# medal.net
KiCad netlist of a schematic drawn in EAGLE
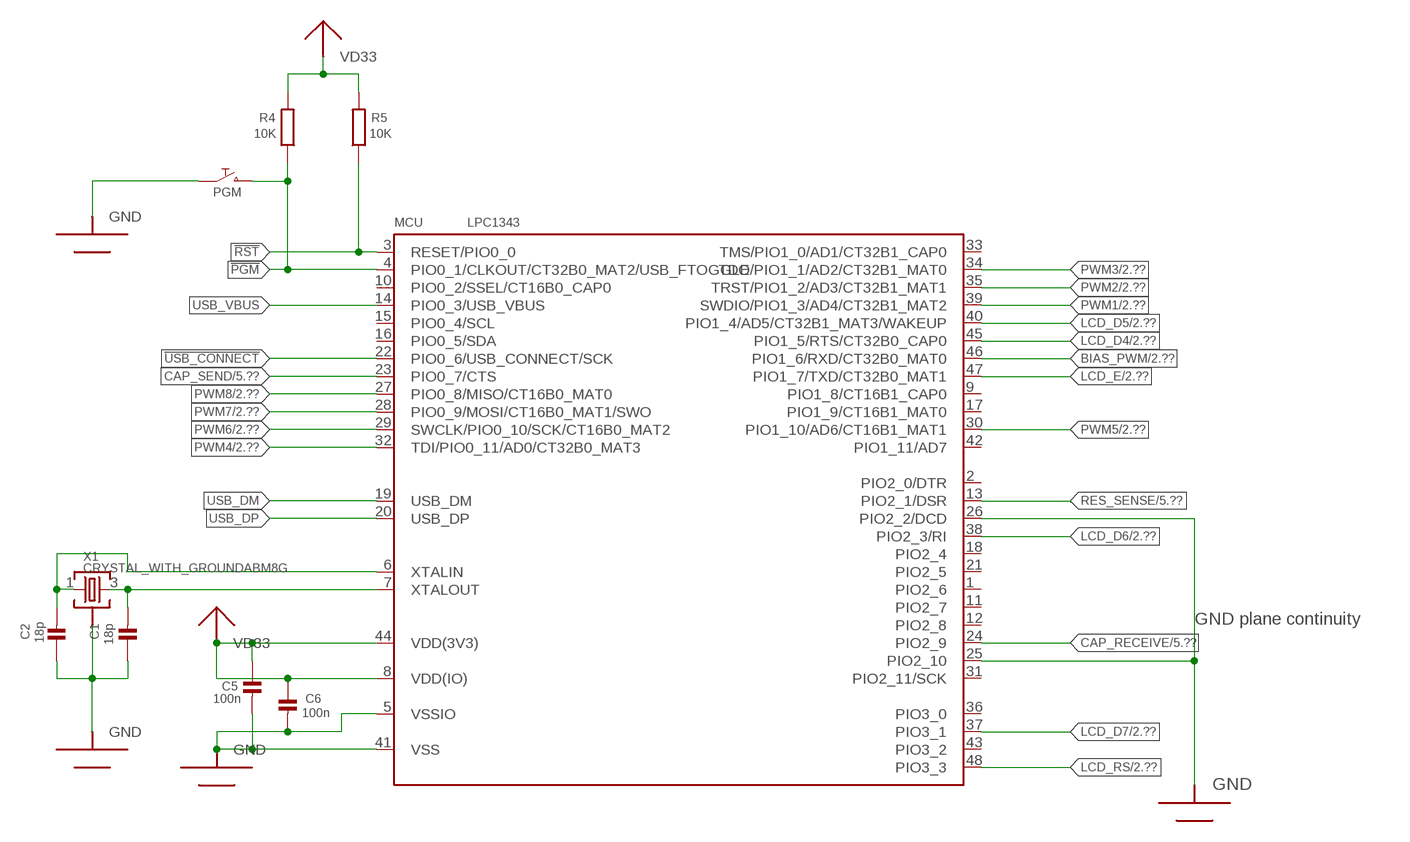
[diagram p0: schematic, sheet 1]
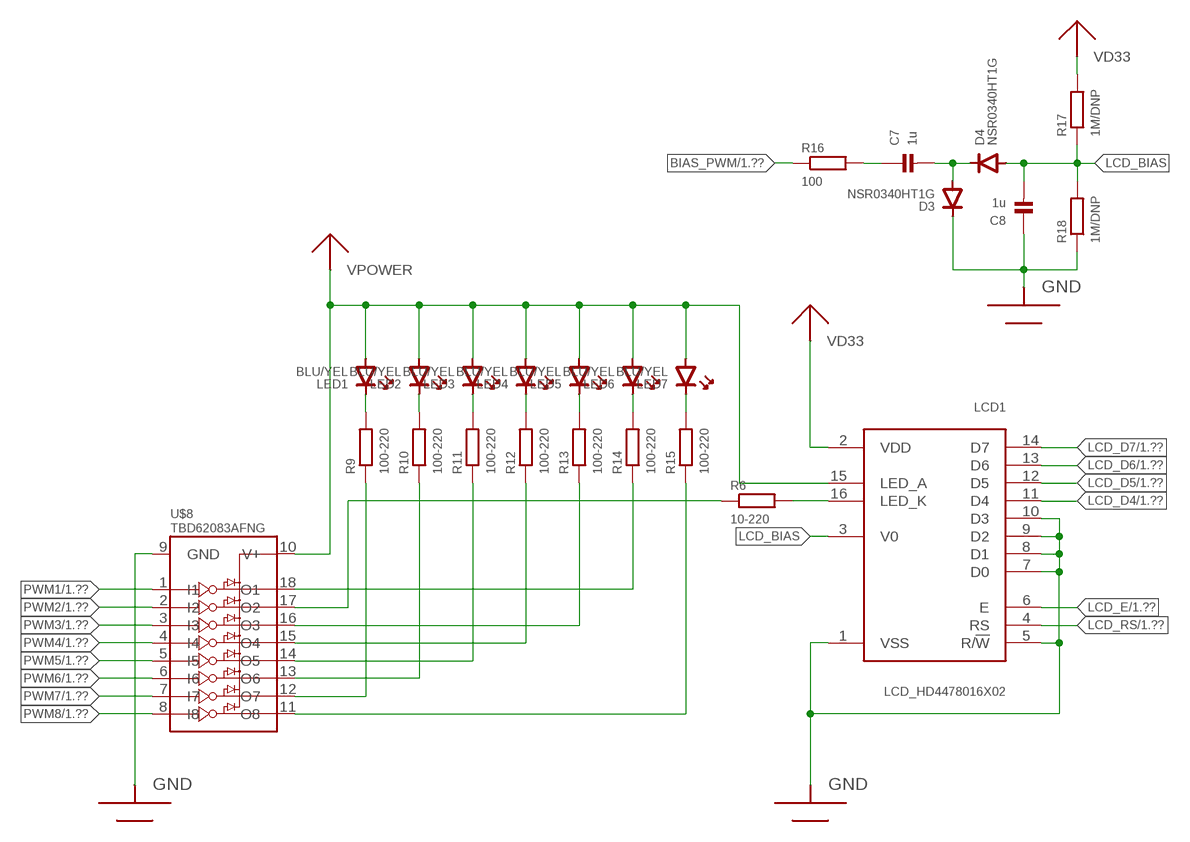
[diagram p1: schematic, sheet 2]
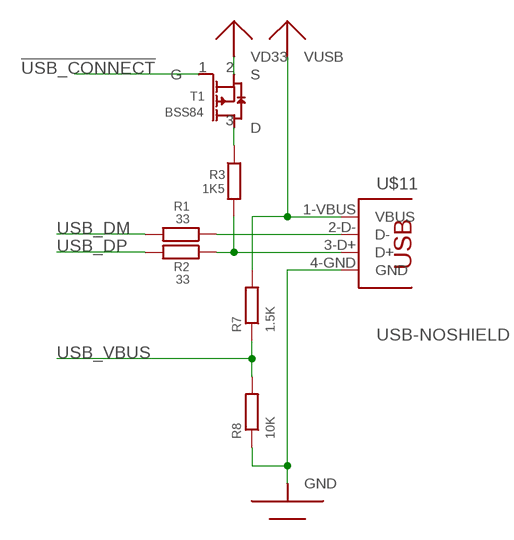
[diagram p2: schematic, sheet 3]
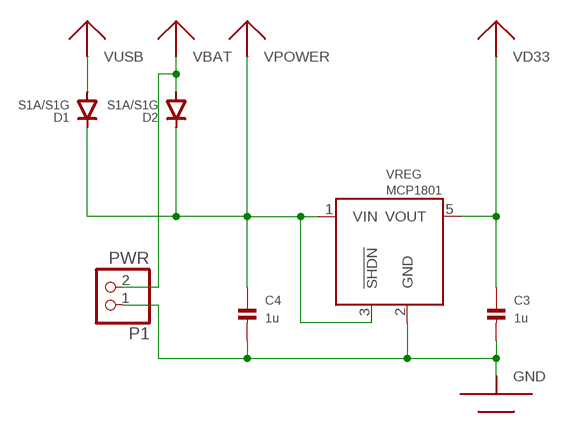
[diagram p3: schematic, sheet 4]
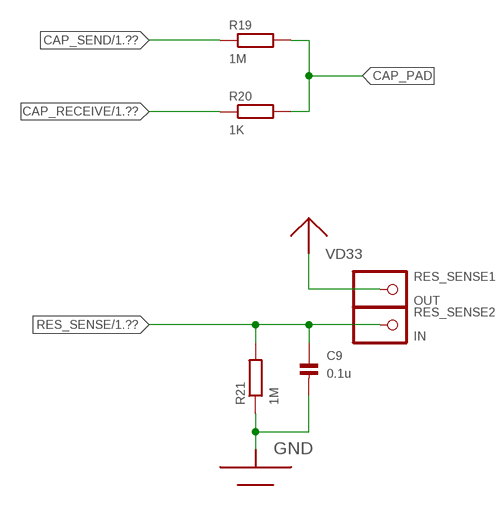
[diagram p4: schematic, sheet 5]

(export (version "E")
  (design (tool "Eeschema 10.0.6"))
  (components
    (comp (ref "C1")
      (value "18p")
      (footprint "eagle-import:0603-NOSILK")
      (libsource (lib "eagle-import") (part "CAP_CERAMIC0603-NOSILK"))
    )
    (comp (ref "C2")
      (value "18p")
      (footprint "eagle-import:0603-NOSILK")
      (libsource (lib "eagle-import") (part "CAP_CERAMIC0603-NOSILK"))
    )
    (comp (ref "C5")
      (value "100n")
      (footprint "eagle-import:0603-NOSILK")
      (libsource (lib "eagle-import") (part "CAP_CERAMIC0603-NOSILK"))
    )
    (comp (ref "C6")
      (value "100n")
      (footprint "eagle-import:0603-NOSILK")
      (libsource (lib "eagle-import") (part "CAP_CERAMIC0603-NOSILK"))
    )
    (comp (ref "MCU")
      (value "LPC1343")
      (footprint "eagle-import:QFP48-0.5-NOSILK")
      (libsource (lib "eagle-import") (part "LPC1343_QFPQFP_NOSILK"))
    )
    (comp (ref "PGM")
      (value "PUSHBUTTONKMR2XX-NOSILK")
      (footprint "eagle-import:CK-KMR2-NOSILK")
      (libsource (lib "eagle-import") (part "PUSHBUTTONKMR2XX-NOSILK"))
    )
    (comp (ref "R4")
      (value "10K")
      (footprint "eagle-import:0603-NOSILK")
      (libsource (lib "eagle-import") (part "R-EU_0603-NOSILK"))
    )
    (comp (ref "R5")
      (value "10K")
      (footprint "eagle-import:0603-NOSILK")
      (libsource (lib "eagle-import") (part "R-EU_0603-NOSILK"))
    )
    (comp (ref "X1")
      (value "CRYSTAL_WITH_GROUNDABM8G")
      (footprint "eagle-import:ABM8G")
      (libsource (lib "eagle-import") (part "CRYSTAL_WITH_GROUNDABM8G"))
    )
    (comp (ref "R1")
      (value "33")
      (footprint "eagle-import:0603-NOSILK")
      (libsource (lib "eagle-import") (part "R-EU_0603-NOSILK"))
    )
    (comp (ref "R2")
      (value "33")
      (footprint "eagle-import:0603-NOSILK")
      (libsource (lib "eagle-import") (part "R-EU_0603-NOSILK"))
    )
    (comp (ref "R3")
      (value "1K5")
      (footprint "eagle-import:0603-NOSILK")
      (libsource (lib "eagle-import") (part "R-EU_0603-NOSILK"))
    )
    (comp (ref "R7")
      (value "1.5K")
      (footprint "eagle-import:0603-NOSILK")
      (libsource (lib "eagle-import") (part "R-EU_0603-NOSILK"))
    )
    (comp (ref "R8")
      (value "10K")
      (footprint "eagle-import:0603-NOSILK")
      (libsource (lib "eagle-import") (part "R-EU_0603-NOSILK"))
    )
    (comp (ref "T1")
      (value "BSS84")
      (footprint "eagle-import:SOT23-NOPLACE")
      (libsource (lib "eagle-import") (part "PMOS_ENHSOT23-NOSILK"))
    )
    (comp (ref "U$11")
      (value "USB-NOSHIELD")
      (footprint "eagle-import:USB-A-PCB")
      (libsource (lib "eagle-import") (part "USB-NOSHIELD"))
    )
    (comp (ref "C7")
      (value "1u")
      (footprint "eagle-import:0603-NOSILK")
      (libsource (lib "eagle-import") (part "CAP_CERAMIC0603-NOSILK"))
    )
    (comp (ref "C8")
      (value "1u")
      (footprint "eagle-import:0603-NOSILK")
      (libsource (lib "eagle-import") (part "CAP_CERAMIC0603-NOSILK"))
    )
    (comp (ref "D3")
      (value "NSR0340HT1G")
      (footprint "eagle-import:SOD323R-NOPLACE")
      (libsource (lib "eagle-import") (part "DIODESOD323R-NOPLACE"))
    )
    (comp (ref "D4")
      (value "NSR0340HT1G")
      (footprint "eagle-import:SOD323R-NOPLACE")
      (libsource (lib "eagle-import") (part "DIODESOD323R-NOPLACE"))
    )
    (comp (ref "LCD1")
      (value "LCD_HD4478016X02")
      (footprint "eagle-import:LCD_16X02")
      (libsource (lib "eagle-import") (part "LCD_HD4478016X02"))
    )
    (comp (ref "LED1")
      (value "BLU/YEL")
      (footprint "eagle-import:0603_POLAR")
      (libsource (lib "eagle-import") (part "LED0603"))
    )
    (comp (ref "LED2")
      (value "BLU/YEL")
      (footprint "eagle-import:0603_POLAR")
      (libsource (lib "eagle-import") (part "LED0603"))
    )
    (comp (ref "LED3")
      (value "BLU/YEL")
      (footprint "eagle-import:0603_POLAR")
      (libsource (lib "eagle-import") (part "LED0603"))
    )
    (comp (ref "LED4")
      (value "BLU/YEL")
      (footprint "eagle-import:0603_POLAR")
      (libsource (lib "eagle-import") (part "LED0603"))
    )
    (comp (ref "LED5")
      (value "BLU/YEL")
      (footprint "eagle-import:0603_POLAR")
      (libsource (lib "eagle-import") (part "LED0603"))
    )
    (comp (ref "LED6")
      (value "BLU/YEL")
      (footprint "eagle-import:0603_POLAR")
      (libsource (lib "eagle-import") (part "LED0603"))
    )
    (comp (ref "LED7")
      (value "BLU/YEL")
      (footprint "eagle-import:0603_POLAR")
      (libsource (lib "eagle-import") (part "LED0603"))
    )
    (comp (ref "R6")
      (value "10-220")
      (footprint "eagle-import:1206-NOSILK")
      (libsource (lib "eagle-import") (part "R-EU_1206-NOSILK"))
    )
    (comp (ref "R9")
      (value "100-220")
      (footprint "eagle-import:0603-NOSILK")
      (libsource (lib "eagle-import") (part "R-EU_0603-NOSILK"))
    )
    (comp (ref "R10")
      (value "100-220")
      (footprint "eagle-import:0603-NOSILK")
      (libsource (lib "eagle-import") (part "R-EU_0603-NOSILK"))
    )
    (comp (ref "R11")
      (value "100-220")
      (footprint "eagle-import:0603-NOSILK")
      (libsource (lib "eagle-import") (part "R-EU_0603-NOSILK"))
    )
    (comp (ref "R12")
      (value "100-220")
      (footprint "eagle-import:0603-NOSILK")
      (libsource (lib "eagle-import") (part "R-EU_0603-NOSILK"))
    )
    (comp (ref "R13")
      (value "100-220")
      (footprint "eagle-import:0603-NOSILK")
      (libsource (lib "eagle-import") (part "R-EU_0603-NOSILK"))
    )
    (comp (ref "R14")
      (value "100-220")
      (footprint "eagle-import:0603-NOSILK")
      (libsource (lib "eagle-import") (part "R-EU_0603-NOSILK"))
    )
    (comp (ref "R15")
      (value "100-220")
      (footprint "eagle-import:0603-NOSILK")
      (libsource (lib "eagle-import") (part "R-EU_0603-NOSILK"))
    )
    (comp (ref "R16")
      (value "100")
      (footprint "eagle-import:0603-NOSILK")
      (libsource (lib "eagle-import") (part "R-EU_0603-NOSILK"))
    )
    (comp (ref "R17")
      (value "1M/DNP")
      (footprint "eagle-import:0603-NOSILK")
      (libsource (lib "eagle-import") (part "R-EU_0603-NOSILK"))
    )
    (comp (ref "R18")
      (value "1M/DNP")
      (footprint "eagle-import:0603-NOSILK")
      (libsource (lib "eagle-import") (part "R-EU_0603-NOSILK"))
    )
    (comp (ref "U$8")
      (value "TBD62083AFNG")
      (footprint "eagle-import:SSOP18-4.4-0.65-NOPLACE")
      (libsource (lib "eagle-import") (part "LOW_SIDE_DRIVERX8NOPLACE"))
    )
    (comp (ref "C9")
      (value "0.1u")
      (footprint "eagle-import:0603-NOSILK")
      (libsource (lib "eagle-import") (part "CAP_CERAMIC0603-NOSILK"))
    )
    (comp (ref "R19")
      (value "1M")
      (footprint "eagle-import:0603-NOSILK")
      (libsource (lib "eagle-import") (part "R-EU_0603-NOSILK"))
    )
    (comp (ref "R20")
      (value "1K")
      (footprint "eagle-import:0603-NOSILK")
      (libsource (lib "eagle-import") (part "R-EU_0603-NOSILK"))
    )
    (comp (ref "R21")
      (value "1M")
      (footprint "eagle-import:0603-NOSILK")
      (libsource (lib "eagle-import") (part "R-EU_0603-NOSILK"))
    )
    (comp (ref "RES_SENSE1")
      (value "OUT")
      (footprint "eagle-import:1X01_1MM_ROUND")
      (libsource (lib "eagle-import") (part "HEADER-1X1SMALL"))
    )
    (comp (ref "RES_SENSE2")
      (value "IN")
      (footprint "eagle-import:1X01_1MM_ROUND")
      (libsource (lib "eagle-import") (part "HEADER-1X1SMALL"))
    )
    (comp (ref "C3")
      (value "1u")
      (footprint "eagle-import:0603-NOSILK")
      (libsource (lib "eagle-import") (part "CAP_CERAMIC0603-NOSILK"))
    )
    (comp (ref "C4")
      (value "1u")
      (footprint "eagle-import:0603-NOSILK")
      (libsource (lib "eagle-import") (part "CAP_CERAMIC0603-NOSILK"))
    )
    (comp (ref "D1")
      (value "S1A/S1G")
      (footprint "eagle-import:DSMA-NOPLACE")
      (libsource (lib "eagle-import") (part "DIODEDSMA-NOPLACE"))
    )
    (comp (ref "D2")
      (value "S1A/S1G")
      (footprint "eagle-import:DSMA-NOPLACE")
      (libsource (lib "eagle-import") (part "DIODEDSMA-NOPLACE"))
    )
    (comp (ref "P1")
      (value "PWR")
      (footprint "eagle-import:1X02_ROUND")
      (libsource (lib "eagle-import") (part "HEADER-2ROUND"))
    )
    (comp (ref "VREG")
      (value "MCP1801")
      (footprint "eagle-import:SOT-23-5-NOSILK")
      (libsource (lib "eagle-import") (part "LDO_ENABLESOT-23-5-NOSILK"))
    )
  )
  (nets
    (net (code "1") (name "BIAS_PWM") (class "Default")
      (node (ref "MCU") (pin "46") (pinfunction "PIO1_6/RXD/CT32B0_MAT0_46") (pintype "bidirectional"))
      (node (ref "R16") (pin "1") (pinfunction "1_1") (pintype "passive"))
    )
    (net (code "2") (name "CAP_PAD") (class "Default")
      (node (ref "R19") (pin "2") (pinfunction "2_2") (pintype "passive"))
      (node (ref "R20") (pin "2") (pinfunction "2_2") (pintype "passive"))
    )
    (net (code "3") (name "CAP_RECEIVE") (class "Default")
      (node (ref "MCU") (pin "24") (pinfunction "PIO2_9_24") (pintype "bidirectional"))
      (node (ref "R20") (pin "1") (pinfunction "1_1") (pintype "passive"))
    )
    (net (code "4") (name "CAP_SEND") (class "Default")
      (node (ref "MCU") (pin "23") (pinfunction "PIO0_7/CTS_23") (pintype "bidirectional"))
      (node (ref "R19") (pin "1") (pinfunction "1_1") (pintype "passive"))
    )
    (net (code "5") (name "GND") (class "Default")
      (node (ref "C1") (pin "1") (pinfunction "P$1_1") (pintype "passive"))
      (node (ref "C2") (pin "1") (pinfunction "P$1_1") (pintype "passive"))
      (node (ref "C3") (pin "2") (pinfunction "P$2_2") (pintype "passive"))
      (node (ref "C4") (pin "2") (pinfunction "P$2_2") (pintype "passive"))
      (node (ref "C5") (pin "2") (pinfunction "P$2_2") (pintype "passive"))
      (node (ref "C6") (pin "2") (pinfunction "P$2_2") (pintype "passive"))
      (node (ref "C8") (pin "1") (pinfunction "P$1_1") (pintype "passive"))
      (node (ref "C9") (pin "2") (pinfunction "P$2_2") (pintype "passive"))
      (node (ref "D3") (pin "K") (pinfunction "CATHODE_K") (pintype "bidirectional"))
      (node (ref "LCD1") (pin "1") (pinfunction "VSS_1") (pintype "power_in"))
      (node (ref "LCD1") (pin "10") (pinfunction "D3_10") (pintype "bidirectional"))
      (node (ref "LCD1") (pin "5") (pinfunction "R/~{W}_5") (pintype "input"))
      (node (ref "LCD1") (pin "7") (pinfunction "D0_7") (pintype "bidirectional"))
      (node (ref "LCD1") (pin "8") (pinfunction "D1_8") (pintype "bidirectional"))
      (node (ref "LCD1") (pin "9") (pinfunction "D2_9") (pintype "bidirectional"))
      (node (ref "MCU") (pin "25") (pinfunction "PIO2_10_25") (pintype "bidirectional"))
      (node (ref "MCU") (pin "26") (pinfunction "PIO2_2/DCD_26") (pintype "bidirectional"))
      (node (ref "MCU") (pin "41") (pinfunction "VSS_41") (pintype "power_in"))
      (node (ref "MCU") (pin "5") (pinfunction "VSSIO_5") (pintype "power_in"))
      (node (ref "P1") (pin "1") (pinfunction "1_1") (pintype "passive"))
      (node (ref "PGM") (pin "P$1") (pinfunction "1_P$1") (pintype "bidirectional"))
      (node (ref "PGM") (pin "P$2") (pinfunction "1_P$2") (pintype "bidirectional"))
      (node (ref "R18") (pin "1") (pinfunction "1_1") (pintype "passive"))
      (node (ref "R21") (pin "1") (pinfunction "1_1") (pintype "passive"))
      (node (ref "R8") (pin "1") (pinfunction "1_1") (pintype "passive"))
      (node (ref "U$11") (pin "4-GND") (pinfunction "GND_4-GND") (pintype "power_in"))
      (node (ref "U$8") (pin "9") (pinfunction "GND_9") (pintype "bidirectional"))
      (node (ref "VREG") (pin "2") (pinfunction "GND_2") (pintype "power_in"))
      (node (ref "X1") (pin "2") (pinfunction "GND_2") (pintype "power_in"))
      (node (ref "X1") (pin "4") (pinfunction "GND_4") (pintype "power_in"))
    )
    (net (code "6") (name "LCD_BIAS") (class "Default")
      (node (ref "C8") (pin "2") (pinfunction "P$2_2") (pintype "passive"))
      (node (ref "D4") (pin "A") (pinfunction "ANODE_A") (pintype "bidirectional"))
      (node (ref "LCD1") (pin "3") (pinfunction "V0_3") (pintype "input"))
      (node (ref "R17") (pin "1") (pinfunction "1_1") (pintype "passive"))
      (node (ref "R18") (pin "2") (pinfunction "2_2") (pintype "passive"))
    )
    (net (code "7") (name "LCD_D4") (class "Default")
      (node (ref "LCD1") (pin "11") (pinfunction "D4_11") (pintype "bidirectional"))
      (node (ref "MCU") (pin "45") (pinfunction "PIO1_5/RTS/CT32B0_CAP0_45") (pintype "bidirectional"))
    )
    (net (code "8") (name "LCD_D5") (class "Default")
      (node (ref "LCD1") (pin "12") (pinfunction "D5_12") (pintype "bidirectional"))
      (node (ref "MCU") (pin "40") (pinfunction "PIO1_4/AD5/CT32B1_MAT3/WAKEUP_40") (pintype "bidirectional"))
    )
    (net (code "9") (name "LCD_D6") (class "Default")
      (node (ref "LCD1") (pin "13") (pinfunction "D6_13") (pintype "bidirectional"))
      (node (ref "MCU") (pin "38") (pinfunction "PIO2_3/RI_38") (pintype "bidirectional"))
    )
    (net (code "10") (name "LCD_D7") (class "Default")
      (node (ref "LCD1") (pin "14") (pinfunction "D7_14") (pintype "bidirectional"))
      (node (ref "MCU") (pin "37") (pinfunction "PIO3_1_37") (pintype "bidirectional"))
    )
    (net (code "11") (name "LCD_E") (class "Default")
      (node (ref "LCD1") (pin "6") (pinfunction "E_6") (pintype "input"))
      (node (ref "MCU") (pin "47") (pinfunction "PIO1_7/TXD/CT32B0_MAT1_47") (pintype "bidirectional"))
    )
    (net (code "12") (name "LCD_RS") (class "Default")
      (node (ref "LCD1") (pin "4") (pinfunction "RS_4") (pintype "input"))
      (node (ref "MCU") (pin "48") (pinfunction "PIO3_3_48") (pintype "bidirectional"))
    )
    (net (code "13") (name "Net-(C1-P$2)") (class "Default")
      (node (ref "C1") (pin "2") (pinfunction "P$2_2") (pintype "passive"))
      (node (ref "MCU") (pin "7") (pinfunction "XTALOUT_7") (pintype "output"))
      (node (ref "X1") (pin "3") (pinfunction "2_3") (pintype "passive"))
    )
    (net (code "14") (name "Net-(C2-P$2)") (class "Default")
      (node (ref "C2") (pin "2") (pinfunction "P$2_2") (pintype "passive"))
      (node (ref "MCU") (pin "6") (pinfunction "XTALIN_6") (pintype "input"))
      (node (ref "X1") (pin "1") (pinfunction "1_1") (pintype "passive"))
    )
    (net (code "15") (name "Net-(C7-P$1)") (class "Default")
      (node (ref "C7") (pin "1") (pinfunction "P$1_1") (pintype "passive"))
      (node (ref "R16") (pin "2") (pinfunction "2_2") (pintype "passive"))
    )
    (net (code "16") (name "Net-(C7-P$2)") (class "Default")
      (node (ref "C7") (pin "2") (pinfunction "P$2_2") (pintype "passive"))
      (node (ref "D3") (pin "A") (pinfunction "ANODE_A") (pintype "bidirectional"))
      (node (ref "D4") (pin "K") (pinfunction "CATHODE_K") (pintype "bidirectional"))
    )
    (net (code "17") (name "Net-(LCD1-LED_K)") (class "Default")
      (node (ref "LCD1") (pin "16") (pinfunction "LED_K_16") (pintype "input"))
      (node (ref "R6") (pin "2") (pinfunction "2_2") (pintype "passive"))
    )
    (net (code "18") (name "Net-(LED1-CATHODE)") (class "Default")
      (node (ref "LED1") (pin "K") (pinfunction "CATHODE_K") (pintype "bidirectional"))
      (node (ref "R9") (pin "2") (pinfunction "2_2") (pintype "passive"))
    )
    (net (code "19") (name "Net-(LED2-CATHODE)") (class "Default")
      (node (ref "LED2") (pin "K") (pinfunction "CATHODE_K") (pintype "bidirectional"))
      (node (ref "R10") (pin "2") (pinfunction "2_2") (pintype "passive"))
    )
    (net (code "20") (name "Net-(LED3-CATHODE)") (class "Default")
      (node (ref "LED3") (pin "K") (pinfunction "CATHODE_K") (pintype "bidirectional"))
      (node (ref "R11") (pin "2") (pinfunction "2_2") (pintype "passive"))
    )
    (net (code "21") (name "Net-(LED4-CATHODE)") (class "Default")
      (node (ref "LED4") (pin "K") (pinfunction "CATHODE_K") (pintype "bidirectional"))
      (node (ref "R12") (pin "2") (pinfunction "2_2") (pintype "passive"))
    )
    (net (code "22") (name "Net-(LED5-CATHODE)") (class "Default")
      (node (ref "LED5") (pin "K") (pinfunction "CATHODE_K") (pintype "bidirectional"))
      (node (ref "R13") (pin "2") (pinfunction "2_2") (pintype "passive"))
    )
    (net (code "23") (name "Net-(LED6-CATHODE)") (class "Default")
      (node (ref "LED6") (pin "K") (pinfunction "CATHODE_K") (pintype "bidirectional"))
      (node (ref "R14") (pin "2") (pinfunction "2_2") (pintype "passive"))
    )
    (net (code "24") (name "Net-(LED7-CATHODE)") (class "Default")
      (node (ref "LED7") (pin "K") (pinfunction "CATHODE_K") (pintype "bidirectional"))
      (node (ref "R15") (pin "2") (pinfunction "2_2") (pintype "passive"))
    )
    (net (code "25") (name "Net-(T1-D)") (class "Default")
      (node (ref "R3") (pin "1") (pinfunction "1_1") (pintype "passive"))
      (node (ref "T1") (pin "3") (pinfunction "D_3") (pintype "bidirectional"))
    )
    (net (code "26") (name "Net-(U$8-O1)") (class "Default")
      (node (ref "R14") (pin "1") (pinfunction "1_1") (pintype "passive"))
      (node (ref "U$8") (pin "18") (pinfunction "O1_18") (pintype "bidirectional"))
    )
    (net (code "27") (name "Net-(U$8-O2)") (class "Default")
      (node (ref "R6") (pin "1") (pinfunction "1_1") (pintype "passive"))
      (node (ref "U$8") (pin "17") (pinfunction "O2_17") (pintype "bidirectional"))
    )
    (net (code "28") (name "Net-(U$8-O3)") (class "Default")
      (node (ref "R13") (pin "1") (pinfunction "1_1") (pintype "passive"))
      (node (ref "U$8") (pin "16") (pinfunction "O3_16") (pintype "bidirectional"))
    )
    (net (code "29") (name "Net-(U$8-O4)") (class "Default")
      (node (ref "R12") (pin "1") (pinfunction "1_1") (pintype "passive"))
      (node (ref "U$8") (pin "15") (pinfunction "O4_15") (pintype "bidirectional"))
    )
    (net (code "30") (name "Net-(U$8-O5)") (class "Default")
      (node (ref "R11") (pin "1") (pinfunction "1_1") (pintype "passive"))
      (node (ref "U$8") (pin "14") (pinfunction "O5_14") (pintype "bidirectional"))
    )
    (net (code "31") (name "Net-(U$8-O6)") (class "Default")
      (node (ref "R10") (pin "1") (pinfunction "1_1") (pintype "passive"))
      (node (ref "U$8") (pin "13") (pinfunction "O6_13") (pintype "bidirectional"))
    )
    (net (code "32") (name "Net-(U$8-O7)") (class "Default")
      (node (ref "R9") (pin "1") (pinfunction "1_1") (pintype "passive"))
      (node (ref "U$8") (pin "12") (pinfunction "O7_12") (pintype "bidirectional"))
    )
    (net (code "33") (name "Net-(U$8-O8)") (class "Default")
      (node (ref "R15") (pin "1") (pinfunction "1_1") (pintype "passive"))
      (node (ref "U$8") (pin "11") (pinfunction "O8_11") (pintype "bidirectional"))
    )
    (net (code "34") (name "Net-(U$11-D+)") (class "Default")
      (node (ref "R2") (pin "1") (pinfunction "1_1") (pintype "passive"))
      (node (ref "R3") (pin "2") (pinfunction "2_2") (pintype "passive"))
      (node (ref "U$11") (pin "3-D+") (pinfunction "D+_3-D+") (pintype "bidirectional"))
    )
    (net (code "35") (name "Net-(U$11-D-)") (class "Default")
      (node (ref "R1") (pin "1") (pinfunction "1_1") (pintype "passive"))
      (node (ref "U$11") (pin "2-D-") (pinfunction "D-_2-D-") (pintype "bidirectional"))
    )
    (net (code "36") (name "PWM1") (class "Default")
      (node (ref "MCU") (pin "39") (pinfunction "SWDIO/PIO1_3/AD4/CT32B1_MAT2_39") (pintype "bidirectional"))
      (node (ref "U$8") (pin "1") (pinfunction "I1_1") (pintype "bidirectional"))
    )
    (net (code "37") (name "PWM2") (class "Default")
      (node (ref "MCU") (pin "35") (pinfunction "TRST/PIO1_2/AD3/CT32B1_MAT1_35") (pintype "bidirectional"))
      (node (ref "U$8") (pin "2") (pinfunction "I2_2") (pintype "bidirectional"))
    )
    (net (code "38") (name "PWM3") (class "Default")
      (node (ref "MCU") (pin "34") (pinfunction "TDO/PIO1_1/AD2/CT32B1_MAT0_34") (pintype "bidirectional"))
      (node (ref "U$8") (pin "3") (pinfunction "I3_3") (pintype "bidirectional"))
    )
    (net (code "39") (name "PWM4") (class "Default")
      (node (ref "MCU") (pin "32") (pinfunction "TDI/PIO0_11/AD0/CT32B0_MAT3_32") (pintype "bidirectional"))
      (node (ref "U$8") (pin "4") (pinfunction "I4_4") (pintype "bidirectional"))
    )
    (net (code "40") (name "PWM5") (class "Default")
      (node (ref "MCU") (pin "30") (pinfunction "PIO1_10/AD6/CT16B1_MAT1_30") (pintype "bidirectional"))
      (node (ref "U$8") (pin "5") (pinfunction "I5_5") (pintype "bidirectional"))
    )
    (net (code "41") (name "PWM6") (class "Default")
      (node (ref "MCU") (pin "29") (pinfunction "SWCLK/PIO0_10/SCK/CT16B0_MAT2_29") (pintype "bidirectional"))
      (node (ref "U$8") (pin "6") (pinfunction "I6_6") (pintype "bidirectional"))
    )
    (net (code "42") (name "PWM7") (class "Default")
      (node (ref "MCU") (pin "28") (pinfunction "PIO0_9/MOSI/CT16B0_MAT1/SWO_28") (pintype "bidirectional"))
      (node (ref "U$8") (pin "7") (pinfunction "I7_7") (pintype "bidirectional"))
    )
    (net (code "43") (name "PWM8") (class "Default")
      (node (ref "MCU") (pin "27") (pinfunction "PIO0_8/MISO/CT16B0_MAT0_27") (pintype "bidirectional"))
      (node (ref "U$8") (pin "8") (pinfunction "I8_8") (pintype "bidirectional"))
    )
    (net (code "44") (name "RES_SENSE") (class "Default")
      (node (ref "C9") (pin "1") (pinfunction "P$1_1") (pintype "passive"))
      (node (ref "MCU") (pin "13") (pinfunction "PIO2_1/DSR_13") (pintype "bidirectional"))
      (node (ref "R21") (pin "2") (pinfunction "2_2") (pintype "passive"))
      (node (ref "RES_SENSE2") (pin "P$2") (pinfunction "1_P$2") (pintype "passive"))
    )
    (net (code "45") (name "USB_DM") (class "Default")
      (node (ref "MCU") (pin "19") (pinfunction "USB_DM_19") (pintype "bidirectional"))
      (node (ref "R1") (pin "2") (pinfunction "2_2") (pintype "passive"))
    )
    (net (code "46") (name "USB_DP") (class "Default")
      (node (ref "MCU") (pin "20") (pinfunction "USB_DP_20") (pintype "bidirectional"))
      (node (ref "R2") (pin "2") (pinfunction "2_2") (pintype "passive"))
    )
    (net (code "47") (name "USB_VBUS") (class "Default")
      (node (ref "MCU") (pin "14") (pinfunction "PIO0_3/USB_VBUS_14") (pintype "bidirectional"))
      (node (ref "R7") (pin "1") (pinfunction "1_1") (pintype "passive"))
      (node (ref "R8") (pin "2") (pinfunction "2_2") (pintype "passive"))
    )
    (net (code "48") (name "VBAT") (class "Default")
      (node (ref "D2") (pin "A") (pinfunction "ANODE_A") (pintype "bidirectional"))
      (node (ref "P1") (pin "2") (pinfunction "2_2") (pintype "passive"))
    )
    (net (code "49") (name "VD33") (class "Default")
      (node (ref "C3") (pin "1") (pinfunction "P$1_1") (pintype "passive"))
      (node (ref "C5") (pin "1") (pinfunction "P$1_1") (pintype "passive"))
      (node (ref "C6") (pin "1") (pinfunction "P$1_1") (pintype "passive"))
      (node (ref "LCD1") (pin "2") (pinfunction "VDD_2") (pintype "power_in"))
      (node (ref "MCU") (pin "44") (pinfunction "VDD(3V3)_44") (pintype "power_in"))
      (node (ref "MCU") (pin "8") (pinfunction "VDD(IO)_8") (pintype "power_in"))
      (node (ref "R17") (pin "2") (pinfunction "2_2") (pintype "passive"))
      (node (ref "R4") (pin "2") (pinfunction "2_2") (pintype "passive"))
      (node (ref "R5") (pin "2") (pinfunction "2_2") (pintype "passive"))
      (node (ref "RES_SENSE1") (pin "P$2") (pinfunction "1_P$2") (pintype "passive"))
      (node (ref "T1") (pin "2") (pinfunction "S_2") (pintype "bidirectional"))
      (node (ref "VREG") (pin "5") (pinfunction "VOUT_5") (pintype "power_in"))
    )
    (net (code "50") (name "VPOWER") (class "Default")
      (node (ref "C4") (pin "1") (pinfunction "P$1_1") (pintype "passive"))
      (node (ref "D1") (pin "C") (pinfunction "CATHODE_C") (pintype "bidirectional"))
      (node (ref "D2") (pin "C") (pinfunction "CATHODE_C") (pintype "bidirectional"))
      (node (ref "LCD1") (pin "15") (pinfunction "LED_A_15") (pintype "input"))
      (node (ref "LED1") (pin "A") (pinfunction "ANODE_A") (pintype "bidirectional"))
      (node (ref "LED2") (pin "A") (pinfunction "ANODE_A") (pintype "bidirectional"))
      (node (ref "LED3") (pin "A") (pinfunction "ANODE_A") (pintype "bidirectional"))
      (node (ref "LED4") (pin "A") (pinfunction "ANODE_A") (pintype "bidirectional"))
      (node (ref "LED5") (pin "A") (pinfunction "ANODE_A") (pintype "bidirectional"))
      (node (ref "LED6") (pin "A") (pinfunction "ANODE_A") (pintype "bidirectional"))
      (node (ref "LED7") (pin "A") (pinfunction "ANODE_A") (pintype "bidirectional"))
      (node (ref "U$8") (pin "10") (pinfunction "V+_10") (pintype "bidirectional"))
      (node (ref "VREG") (pin "1") (pinfunction "VIN_1") (pintype "power_in"))
      (node (ref "VREG") (pin "3") (pinfunction "~{SHDN}_3") (pintype "input"))
    )
    (net (code "51") (name "VUSB") (class "Default")
      (node (ref "D1") (pin "A") (pinfunction "ANODE_A") (pintype "bidirectional"))
      (node (ref "R7") (pin "2") (pinfunction "2_2") (pintype "passive"))
      (node (ref "U$11") (pin "1-VBUS") (pinfunction "VBUS_1-VBUS") (pintype "power_in"))
    )
    (net (code "52") (name "unconnected-(MCU-PIO0_2{slash}SSEL{slash}CT16B0_CAP0-Pad10)") (class "Default")
      (node (ref "MCU") (pin "10") (pinfunction "PIO0_2/SSEL/CT16B0_CAP0_10") (pintype "bidirectional"))
    )
    (net (code "53") (name "unconnected-(MCU-PIO0_4{slash}SCL-Pad15)") (class "Default")
      (node (ref "MCU") (pin "15") (pinfunction "PIO0_4/SCL_15") (pintype "bidirectional"))
    )
    (net (code "54") (name "unconnected-(MCU-PIO0_5{slash}SDA-Pad16)") (class "Default")
      (node (ref "MCU") (pin "16") (pinfunction "PIO0_5/SDA_16") (pintype "bidirectional"))
    )
    (net (code "55") (name "unconnected-(MCU-PIO1_8{slash}CT16B1_CAP0-Pad9)") (class "Default")
      (node (ref "MCU") (pin "9") (pinfunction "PIO1_8/CT16B1_CAP0_9") (pintype "bidirectional"))
    )
    (net (code "56") (name "unconnected-(MCU-PIO1_9{slash}CT16B1_MAT0-Pad17)") (class "Default")
      (node (ref "MCU") (pin "17") (pinfunction "PIO1_9/CT16B1_MAT0_17") (pintype "bidirectional"))
    )
    (net (code "57") (name "unconnected-(MCU-PIO1_11{slash}AD7-Pad42)") (class "Default")
      (node (ref "MCU") (pin "42") (pinfunction "PIO1_11/AD7_42") (pintype "bidirectional"))
    )
    (net (code "58") (name "unconnected-(MCU-PIO2_0{slash}DTR-Pad2)") (class "Default")
      (node (ref "MCU") (pin "2") (pinfunction "PIO2_0/DTR_2") (pintype "bidirectional"))
    )
    (net (code "59") (name "unconnected-(MCU-PIO2_4-Pad18)") (class "Default")
      (node (ref "MCU") (pin "18") (pinfunction "PIO2_4_18") (pintype "bidirectional"))
    )
    (net (code "60") (name "unconnected-(MCU-PIO2_5-Pad21)") (class "Default")
      (node (ref "MCU") (pin "21") (pinfunction "PIO2_5_21") (pintype "bidirectional"))
    )
    (net (code "61") (name "unconnected-(MCU-PIO2_6-Pad1)") (class "Default")
      (node (ref "MCU") (pin "1") (pinfunction "PIO2_6_1") (pintype "bidirectional"))
    )
    (net (code "62") (name "unconnected-(MCU-PIO2_7-Pad11)") (class "Default")
      (node (ref "MCU") (pin "11") (pinfunction "PIO2_7_11") (pintype "bidirectional"))
    )
    (net (code "63") (name "unconnected-(MCU-PIO2_8-Pad12)") (class "Default")
      (node (ref "MCU") (pin "12") (pinfunction "PIO2_8_12") (pintype "bidirectional"))
    )
    (net (code "64") (name "unconnected-(MCU-PIO2_11{slash}SCK-Pad31)") (class "Default")
      (node (ref "MCU") (pin "31") (pinfunction "PIO2_11/SCK_31") (pintype "bidirectional"))
    )
    (net (code "65") (name "unconnected-(MCU-PIO3_0-Pad36)") (class "Default")
      (node (ref "MCU") (pin "36") (pinfunction "PIO3_0_36") (pintype "bidirectional"))
    )
    (net (code "66") (name "unconnected-(MCU-PIO3_2-Pad43)") (class "Default")
      (node (ref "MCU") (pin "43") (pinfunction "PIO3_2_43") (pintype "bidirectional"))
    )
    (net (code "67") (name "unconnected-(MCU-TMS{slash}PIO1_0{slash}AD1{slash}CT32B1_CAP0-Pad33)") (class "Default")
      (node (ref "MCU") (pin "33") (pinfunction "TMS/PIO1_0/AD1/CT32B1_CAP0_33") (pintype "bidirectional"))
    )
    (net (code "68") (name "~{PGM}") (class "Default")
      (node (ref "MCU") (pin "4") (pinfunction "PIO0_1/CLKOUT/CT32B0_MAT2/USB_FTOGGLE_4") (pintype "bidirectional"))
      (node (ref "PGM") (pin "P$3") (pinfunction "2_P$3") (pintype "bidirectional"))
      (node (ref "PGM") (pin "P$4") (pinfunction "2_P$4") (pintype "bidirectional"))
      (node (ref "R4") (pin "1") (pinfunction "1_1") (pintype "passive"))
    )
    (net (code "69") (name "~{RST}") (class "Default")
      (node (ref "MCU") (pin "3") (pinfunction "RESET/PIO0_0_3") (pintype "bidirectional"))
      (node (ref "R5") (pin "1") (pinfunction "1_1") (pintype "passive"))
    )
    (net (code "70") (name "~{USB_CONNECT}") (class "Default")
      (node (ref "MCU") (pin "22") (pinfunction "PIO0_6/USB_CONNECT/SCK_22") (pintype "bidirectional"))
      (node (ref "T1") (pin "1") (pinfunction "G_1") (pintype "bidirectional"))
    )
  )
)
